# Bench_Controller.net
KiCad netlist of a schematic drawn in EAGLE
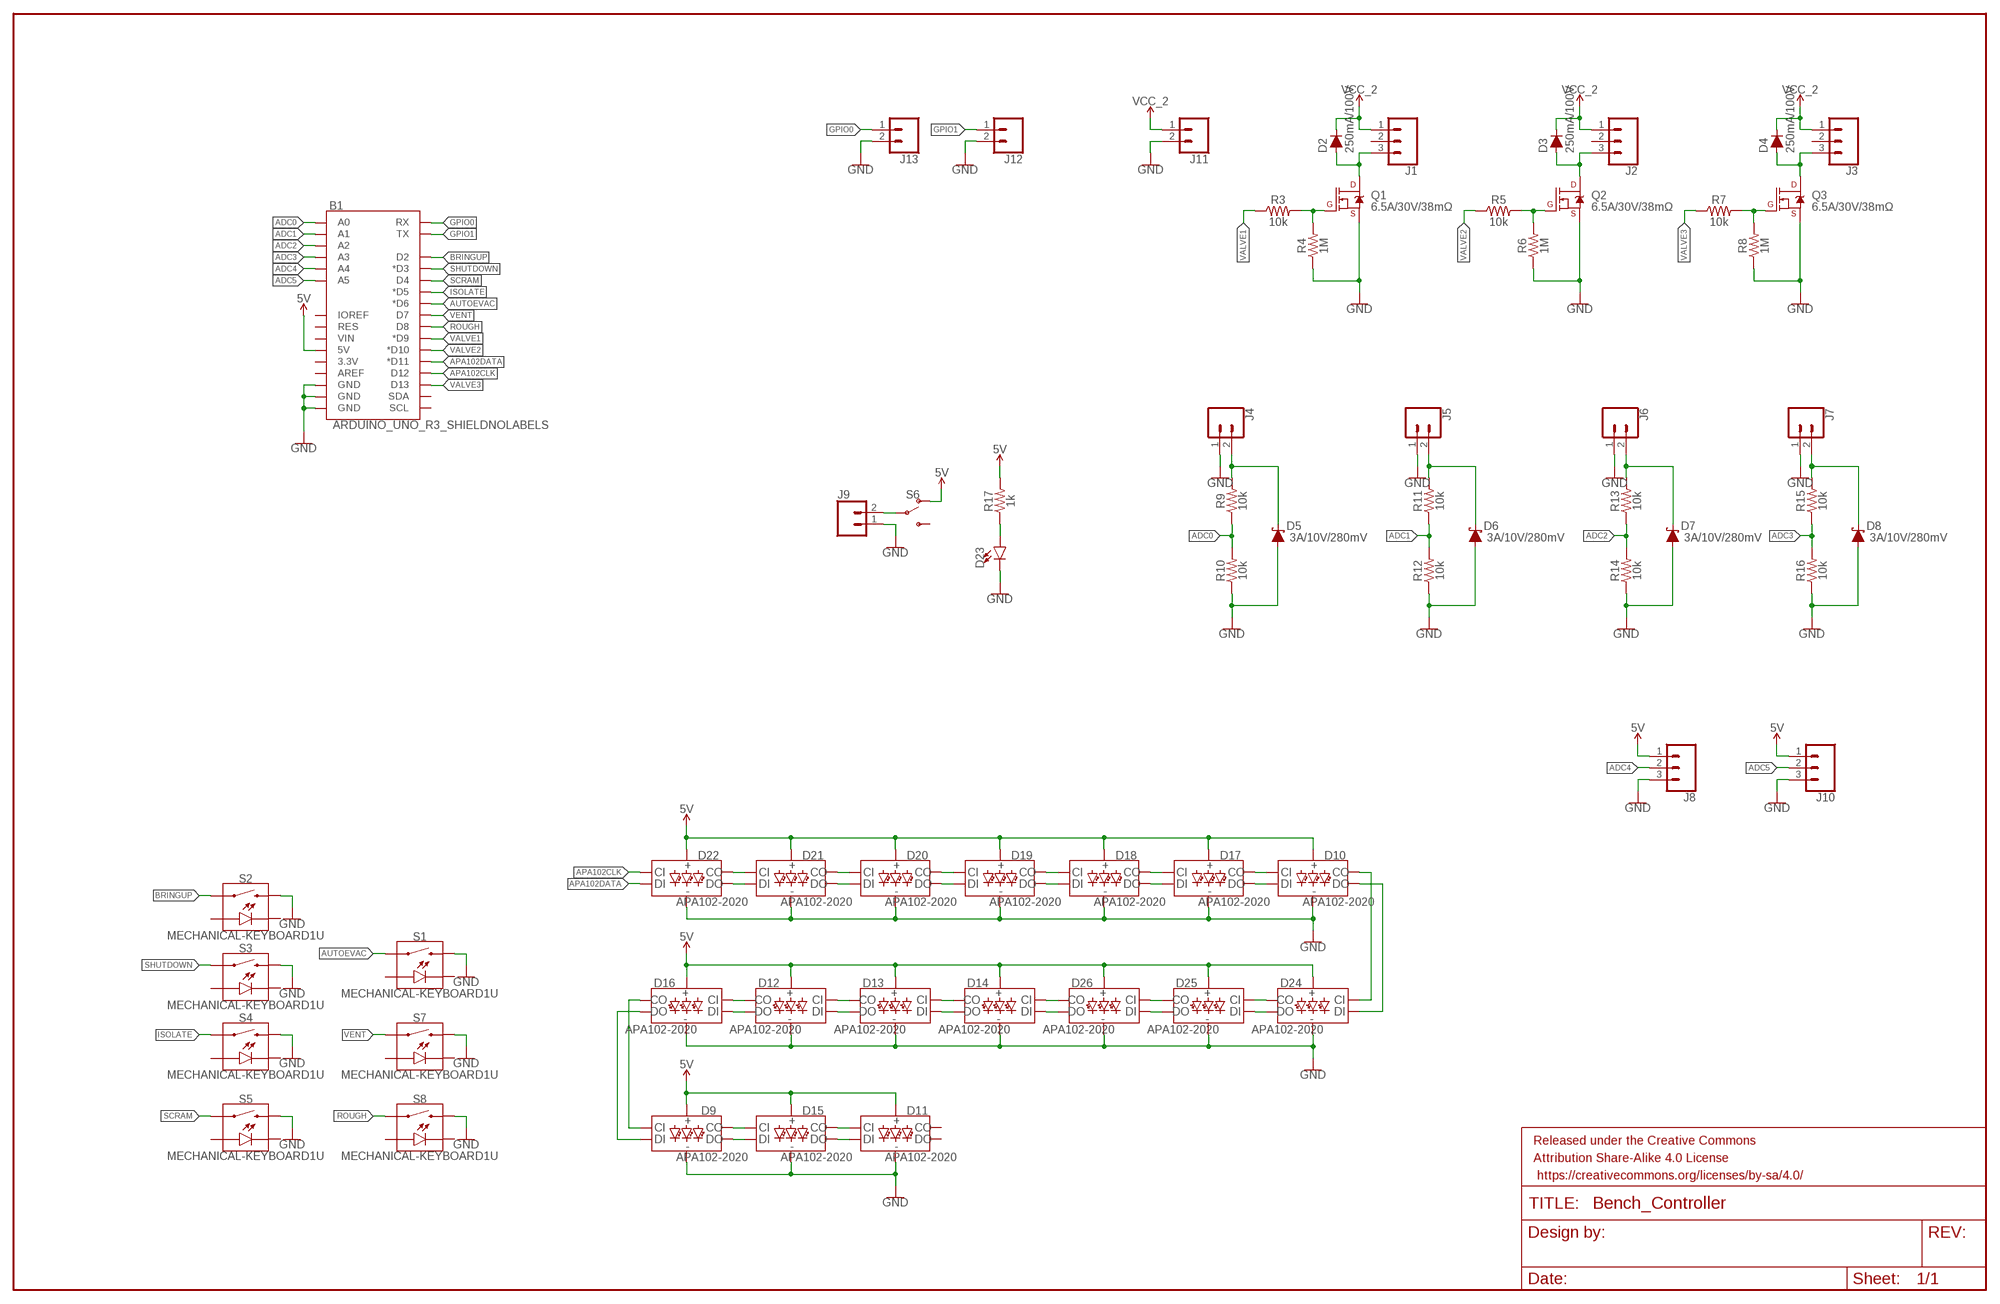
[diagram p0: schematic, sheet 1]

(export (version "E")
  (design (tool "Eeschema 10.0.6"))
  (components
    (comp (ref "B1")
      (value "ARDUINO_UNO_R3_SHIELDNOLABELS")
      (footprint "eagle-import:UNO_R3_SHIELD_NOLABELS")
      (libsource (lib "eagle-import") (part "ARDUINO_UNO_R3_SHIELDNOLABELS"))
    )
    (comp (ref "D2")
      (value "250mA/100V")
      (footprint "eagle-import:SOD-323")
      (libsource (lib "eagle-import") (part "DIODE-BAS16J"))
    )
    (comp (ref "D3")
      (value "250mA/100V")
      (footprint "eagle-import:SOD-323")
      (libsource (lib "eagle-import") (part "DIODE-BAS16J"))
    )
    (comp (ref "D4")
      (value "250mA/100V")
      (footprint "eagle-import:SOD-323")
      (libsource (lib "eagle-import") (part "DIODE-BAS16J"))
    )
    (comp (ref "D5")
      (value "3A/10V/280mV")
      (footprint "eagle-import:SOD-323")
      (libsource (lib "eagle-import") (part "DIODE-SCHOTTKY-BAT60A"))
    )
    (comp (ref "D6")
      (value "3A/10V/280mV")
      (footprint "eagle-import:SOD-323")
      (libsource (lib "eagle-import") (part "DIODE-SCHOTTKY-BAT60A"))
    )
    (comp (ref "D7")
      (value "3A/10V/280mV")
      (footprint "eagle-import:SOD-323")
      (libsource (lib "eagle-import") (part "DIODE-SCHOTTKY-BAT60A"))
    )
    (comp (ref "D8")
      (value "3A/10V/280mV")
      (footprint "eagle-import:SOD-323")
      (libsource (lib "eagle-import") (part "DIODE-SCHOTTKY-BAT60A"))
    )
    (comp (ref "D9")
      (value "APA102-2020")
      (footprint "eagle-import:APA102-2020")
      (libsource (lib "eagle-import") (part "APA102-2020"))
    )
    (comp (ref "D10")
      (value "APA102-2020")
      (footprint "eagle-import:APA102-2020")
      (libsource (lib "eagle-import") (part "APA102-2020"))
    )
    (comp (ref "D11")
      (value "APA102-2020")
      (footprint "eagle-import:APA102-2020")
      (libsource (lib "eagle-import") (part "APA102-2020"))
    )
    (comp (ref "D12")
      (value "APA102-2020")
      (footprint "eagle-import:APA102-2020")
      (libsource (lib "eagle-import") (part "APA102-2020"))
    )
    (comp (ref "D13")
      (value "APA102-2020")
      (footprint "eagle-import:APA102-2020")
      (libsource (lib "eagle-import") (part "APA102-2020"))
    )
    (comp (ref "D14")
      (value "APA102-2020")
      (footprint "eagle-import:APA102-2020")
      (libsource (lib "eagle-import") (part "APA102-2020"))
    )
    (comp (ref "D15")
      (value "APA102-2020")
      (footprint "eagle-import:APA102-2020")
      (libsource (lib "eagle-import") (part "APA102-2020"))
    )
    (comp (ref "D16")
      (value "APA102-2020")
      (footprint "eagle-import:APA102-2020")
      (libsource (lib "eagle-import") (part "APA102-2020"))
    )
    (comp (ref "D17")
      (value "APA102-2020")
      (footprint "eagle-import:APA102-2020")
      (libsource (lib "eagle-import") (part "APA102-2020"))
    )
    (comp (ref "D18")
      (value "APA102-2020")
      (footprint "eagle-import:APA102-2020")
      (libsource (lib "eagle-import") (part "APA102-2020"))
    )
    (comp (ref "D19")
      (value "APA102-2020")
      (footprint "eagle-import:APA102-2020")
      (libsource (lib "eagle-import") (part "APA102-2020"))
    )
    (comp (ref "D20")
      (value "APA102-2020")
      (footprint "eagle-import:APA102-2020")
      (libsource (lib "eagle-import") (part "APA102-2020"))
    )
    (comp (ref "D21")
      (value "APA102-2020")
      (footprint "eagle-import:APA102-2020")
      (libsource (lib "eagle-import") (part "APA102-2020"))
    )
    (comp (ref "D22")
      (value "APA102-2020")
      (footprint "eagle-import:APA102-2020")
      (libsource (lib "eagle-import") (part "APA102-2020"))
    )
    (comp (ref "D23")
      (value "LED5MM")
      (footprint "eagle-import:LED_5MM")
      (libsource (lib "eagle-import") (part "LED5MM"))
    )
    (comp (ref "D24")
      (value "APA102-2020")
      (footprint "eagle-import:APA102-2020")
      (libsource (lib "eagle-import") (part "APA102-2020"))
    )
    (comp (ref "D25")
      (value "APA102-2020")
      (footprint "eagle-import:APA102-2020")
      (libsource (lib "eagle-import") (part "APA102-2020"))
    )
    (comp (ref "D26")
      (value "APA102-2020")
      (footprint "eagle-import:APA102-2020")
      (libsource (lib "eagle-import") (part "APA102-2020"))
    )
    (comp (ref "FRAME1")
      (value "FRAME-LEDGER")
      (footprint "eagle-import:CREATIVE_COMMONS")
      (libsource (lib "eagle-import") (part "FRAME-LEDGER"))
    )
    (comp (ref "J1")
      (value "CONN_031X03_NO_SILK")
      (footprint "eagle-import:1X03_NO_SILK")
      (libsource (lib "eagle-import") (part "CONN_031X03_NO_SILK"))
    )
    (comp (ref "J2")
      (value "CONN_031X03_NO_SILK")
      (footprint "eagle-import:1X03_NO_SILK")
      (libsource (lib "eagle-import") (part "CONN_031X03_NO_SILK"))
    )
    (comp (ref "J3")
      (value "CONN_031X03_NO_SILK")
      (footprint "eagle-import:1X03_NO_SILK")
      (libsource (lib "eagle-import") (part "CONN_031X03_NO_SILK"))
    )
    (comp (ref "J4")
      (value "CONN_021X02_NO_SILK")
      (footprint "eagle-import:1X02_NO_SILK")
      (libsource (lib "eagle-import") (part "CONN_021X02_NO_SILK"))
    )
    (comp (ref "J5")
      (value "CONN_021X02_NO_SILK")
      (footprint "eagle-import:1X02_NO_SILK")
      (libsource (lib "eagle-import") (part "CONN_021X02_NO_SILK"))
    )
    (comp (ref "J6")
      (value "CONN_021X02_NO_SILK")
      (footprint "eagle-import:1X02_NO_SILK")
      (libsource (lib "eagle-import") (part "CONN_021X02_NO_SILK"))
    )
    (comp (ref "J7")
      (value "CONN_021X02_NO_SILK")
      (footprint "eagle-import:1X02_NO_SILK")
      (libsource (lib "eagle-import") (part "CONN_021X02_NO_SILK"))
    )
    (comp (ref "J8")
      (value "CONN_031X03_NO_SILK")
      (footprint "eagle-import:1X03_NO_SILK")
      (libsource (lib "eagle-import") (part "CONN_031X03_NO_SILK"))
    )
    (comp (ref "J9")
      (value "CONN_021X02_NO_SILK")
      (footprint "eagle-import:1X02_NO_SILK")
      (libsource (lib "eagle-import") (part "CONN_021X02_NO_SILK"))
    )
    (comp (ref "J10")
      (value "CONN_031X03_NO_SILK")
      (footprint "eagle-import:1X03_NO_SILK")
      (libsource (lib "eagle-import") (part "CONN_031X03_NO_SILK"))
    )
    (comp (ref "J11")
      (value "CONN_021X02_NO_SILK")
      (footprint "eagle-import:1X02_NO_SILK")
      (libsource (lib "eagle-import") (part "CONN_021X02_NO_SILK"))
    )
    (comp (ref "J12")
      (value "CONN_021X02_NO_SILK")
      (footprint "eagle-import:1X02_NO_SILK")
      (libsource (lib "eagle-import") (part "CONN_021X02_NO_SILK"))
    )
    (comp (ref "J13")
      (value "CONN_021X02_NO_SILK")
      (footprint "eagle-import:1X02_NO_SILK")
      (libsource (lib "eagle-import") (part "CONN_021X02_NO_SILK"))
    )
    (comp (ref "Q1")
      (value "6.5A/30V/38mΩ")
      (footprint "eagle-import:SO08")
      (libsource (lib "eagle-import") (part "MOSFET-NCH-FDS6630A"))
    )
    (comp (ref "Q2")
      (value "6.5A/30V/38mΩ")
      (footprint "eagle-import:SO08")
      (libsource (lib "eagle-import") (part "MOSFET-NCH-FDS6630A"))
    )
    (comp (ref "Q3")
      (value "6.5A/30V/38mΩ")
      (footprint "eagle-import:SO08")
      (libsource (lib "eagle-import") (part "MOSFET-NCH-FDS6630A"))
    )
    (comp (ref "R3")
      (value "10k")
      (footprint "eagle-import:0603")
      (libsource (lib "eagle-import") (part "10KOHM-0603-1/10W-1%"))
    )
    (comp (ref "R4")
      (value "1M")
      (footprint "eagle-import:0603")
      (libsource (lib "eagle-import") (part "1MOHM-0603-1/4W-5%"))
    )
    (comp (ref "R5")
      (value "10k")
      (footprint "eagle-import:0603")
      (libsource (lib "eagle-import") (part "10KOHM-0603-1/10W-1%"))
    )
    (comp (ref "R6")
      (value "1M")
      (footprint "eagle-import:0603")
      (libsource (lib "eagle-import") (part "1MOHM-0603-1/4W-5%"))
    )
    (comp (ref "R7")
      (value "10k")
      (footprint "eagle-import:0603")
      (libsource (lib "eagle-import") (part "10KOHM-0603-1/10W-1%"))
    )
    (comp (ref "R8")
      (value "1M")
      (footprint "eagle-import:0603")
      (libsource (lib "eagle-import") (part "1MOHM-0603-1/4W-5%"))
    )
    (comp (ref "R9")
      (value "10k")
      (footprint "eagle-import:0603")
      (libsource (lib "eagle-import") (part "10KOHM-0603-1/10W-1%"))
    )
    (comp (ref "R10")
      (value "10k")
      (footprint "eagle-import:0603")
      (libsource (lib "eagle-import") (part "10KOHM-0603-1/10W-1%"))
    )
    (comp (ref "R11")
      (value "10k")
      (footprint "eagle-import:0603")
      (libsource (lib "eagle-import") (part "10KOHM-0603-1/10W-1%"))
    )
    (comp (ref "R12")
      (value "10k")
      (footprint "eagle-import:0603")
      (libsource (lib "eagle-import") (part "10KOHM-0603-1/10W-1%"))
    )
    (comp (ref "R13")
      (value "10k")
      (footprint "eagle-import:0603")
      (libsource (lib "eagle-import") (part "10KOHM-0603-1/10W-1%"))
    )
    (comp (ref "R14")
      (value "10k")
      (footprint "eagle-import:0603")
      (libsource (lib "eagle-import") (part "10KOHM-0603-1/10W-1%"))
    )
    (comp (ref "R15")
      (value "10k")
      (footprint "eagle-import:0603")
      (libsource (lib "eagle-import") (part "10KOHM-0603-1/10W-1%"))
    )
    (comp (ref "R16")
      (value "10k")
      (footprint "eagle-import:0603")
      (libsource (lib "eagle-import") (part "10KOHM-0603-1/10W-1%"))
    )
    (comp (ref "R17")
      (value "1k")
      (footprint "eagle-import:0603")
      (libsource (lib "eagle-import") (part "1KOHM-0603-1/10W-1%"))
    )
    (comp (ref "S1")
      (value "MECHANICAL-KEYBOARD1U")
      (footprint "eagle-import:CHERRY-MX-LED-1U")
      (libsource (lib "eagle-import") (part "MECHANICAL-KEYBOARD1U"))
    )
    (comp (ref "S2")
      (value "MECHANICAL-KEYBOARD1U")
      (footprint "eagle-import:CHERRY-MX-LED-1U")
      (libsource (lib "eagle-import") (part "MECHANICAL-KEYBOARD1U"))
    )
    (comp (ref "S3")
      (value "MECHANICAL-KEYBOARD1U")
      (footprint "eagle-import:CHERRY-MX-LED-1U")
      (libsource (lib "eagle-import") (part "MECHANICAL-KEYBOARD1U"))
    )
    (comp (ref "S4")
      (value "MECHANICAL-KEYBOARD1U")
      (footprint "eagle-import:CHERRY-MX-LED-1U")
      (libsource (lib "eagle-import") (part "MECHANICAL-KEYBOARD1U"))
    )
    (comp (ref "S5")
      (value "MECHANICAL-KEYBOARD1U")
      (footprint "eagle-import:CHERRY-MX-LED-1U")
      (libsource (lib "eagle-import") (part "MECHANICAL-KEYBOARD1U"))
    )
    (comp (ref "S6")
      (value "SWITCH-SPDT-PTH-11.6X4.0MM")
      (footprint "eagle-import:SWITCH_SPDT_PTH_11.6X4.0MM")
      (libsource (lib "eagle-import") (part "SWITCH-SPDT-PTH-11.6X4.0MM"))
    )
    (comp (ref "S7")
      (value "MECHANICAL-KEYBOARD1U")
      (footprint "eagle-import:CHERRY-MX-LED-1U")
      (libsource (lib "eagle-import") (part "MECHANICAL-KEYBOARD1U"))
    )
    (comp (ref "S8")
      (value "MECHANICAL-KEYBOARD1U")
      (footprint "eagle-import:CHERRY-MX-LED-1U")
      (libsource (lib "eagle-import") (part "MECHANICAL-KEYBOARD1U"))
    )
  )
  (nets
    (net (code "1") (name "5V") (class "Default")
      (node (ref "B1") (pin "5V") (pinfunction "5V_5V") (pintype "bidirectional"))
      (node (ref "D10") (pin "VDD") (pinfunction "VCC_VDD") (pintype "bidirectional"))
      (node (ref "D11") (pin "VDD") (pinfunction "VCC_VDD") (pintype "bidirectional"))
      (node (ref "D12") (pin "VDD") (pinfunction "VCC_VDD") (pintype "bidirectional"))
      (node (ref "D13") (pin "VDD") (pinfunction "VCC_VDD") (pintype "bidirectional"))
      (node (ref "D14") (pin "VDD") (pinfunction "VCC_VDD") (pintype "bidirectional"))
      (node (ref "D15") (pin "VDD") (pinfunction "VCC_VDD") (pintype "bidirectional"))
      (node (ref "D16") (pin "VDD") (pinfunction "VCC_VDD") (pintype "bidirectional"))
      (node (ref "D17") (pin "VDD") (pinfunction "VCC_VDD") (pintype "bidirectional"))
      (node (ref "D18") (pin "VDD") (pinfunction "VCC_VDD") (pintype "bidirectional"))
      (node (ref "D19") (pin "VDD") (pinfunction "VCC_VDD") (pintype "bidirectional"))
      (node (ref "D20") (pin "VDD") (pinfunction "VCC_VDD") (pintype "bidirectional"))
      (node (ref "D21") (pin "VDD") (pinfunction "VCC_VDD") (pintype "bidirectional"))
      (node (ref "D22") (pin "VDD") (pinfunction "VCC_VDD") (pintype "bidirectional"))
      (node (ref "D24") (pin "VDD") (pinfunction "VCC_VDD") (pintype "bidirectional"))
      (node (ref "D25") (pin "VDD") (pinfunction "VCC_VDD") (pintype "bidirectional"))
      (node (ref "D26") (pin "VDD") (pinfunction "VCC_VDD") (pintype "bidirectional"))
      (node (ref "D9") (pin "VDD") (pinfunction "VCC_VDD") (pintype "bidirectional"))
      (node (ref "J10") (pin "1") (pinfunction "1_1") (pintype "passive"))
      (node (ref "J8") (pin "1") (pinfunction "1_1") (pintype "passive"))
      (node (ref "R17") (pin "2") (pinfunction "2_2") (pintype "passive"))
      (node (ref "S6") (pin "1") (pinfunction "O_1") (pintype "passive"))
    )
    (net (code "2") (name "ADC0") (class "Default")
      (node (ref "B1") (pin "A0") (pinfunction "A0_A0") (pintype "bidirectional"))
      (node (ref "R10") (pin "2") (pinfunction "2_2") (pintype "passive"))
      (node (ref "R9") (pin "1") (pinfunction "1_1") (pintype "passive"))
    )
    (net (code "3") (name "ADC1") (class "Default")
      (node (ref "B1") (pin "A1") (pinfunction "A1_A1") (pintype "bidirectional"))
      (node (ref "R11") (pin "1") (pinfunction "1_1") (pintype "passive"))
      (node (ref "R12") (pin "2") (pinfunction "2_2") (pintype "passive"))
    )
    (net (code "4") (name "ADC2") (class "Default")
      (node (ref "B1") (pin "A2") (pinfunction "A2_A2") (pintype "bidirectional"))
      (node (ref "R13") (pin "1") (pinfunction "1_1") (pintype "passive"))
      (node (ref "R14") (pin "2") (pinfunction "2_2") (pintype "passive"))
    )
    (net (code "5") (name "ADC3") (class "Default")
      (node (ref "B1") (pin "A3") (pinfunction "A3_A3") (pintype "bidirectional"))
      (node (ref "R15") (pin "1") (pinfunction "1_1") (pintype "passive"))
      (node (ref "R16") (pin "2") (pinfunction "2_2") (pintype "passive"))
    )
    (net (code "6") (name "ADC4") (class "Default")
      (node (ref "B1") (pin "A4") (pinfunction "A4_A4") (pintype "bidirectional"))
      (node (ref "J8") (pin "2") (pinfunction "2_2") (pintype "passive"))
    )
    (net (code "7") (name "ADC5") (class "Default")
      (node (ref "B1") (pin "A5") (pinfunction "A5_A5") (pintype "bidirectional"))
      (node (ref "J10") (pin "2") (pinfunction "2_2") (pintype "passive"))
    )
    (net (code "8") (name "APA102CLK") (class "Default")
      (node (ref "B1") (pin "D12") (pinfunction "D12_D12") (pintype "bidirectional"))
      (node (ref "D22") (pin "CKI") (pinfunction "CI_CKI") (pintype "bidirectional"))
    )
    (net (code "9") (name "APA102DATA") (class "Default")
      (node (ref "B1") (pin "D11") (pinfunction "*D11_D11") (pintype "bidirectional"))
      (node (ref "D22") (pin "SDI") (pinfunction "DI_SDI") (pintype "bidirectional"))
    )
    (net (code "10") (name "AUTOEVAC") (class "Default")
      (node (ref "B1") (pin "D6") (pinfunction "*D6_D6") (pintype "bidirectional"))
      (node (ref "S1") (pin "S1") (pinfunction "1_S1") (pintype "passive"))
    )
    (net (code "11") (name "BRINGUP") (class "Default")
      (node (ref "B1") (pin "D2") (pinfunction "D2_D2") (pintype "bidirectional"))
      (node (ref "S2") (pin "S1") (pinfunction "1_S1") (pintype "passive"))
    )
    (net (code "12") (name "GND") (class "Default")
      (node (ref "B1") (pin "GND@0") (pinfunction "GND_GND@0") (pintype "bidirectional"))
      (node (ref "B1") (pin "GND@1") (pinfunction "GND_GND@1") (pintype "bidirectional"))
      (node (ref "B1") (pin "GND@2") (pinfunction "GND_GND@2") (pintype "bidirectional"))
      (node (ref "D10") (pin "GND") (pinfunction "GND_GND") (pintype "bidirectional"))
      (node (ref "D11") (pin "GND") (pinfunction "GND_GND") (pintype "bidirectional"))
      (node (ref "D12") (pin "GND") (pinfunction "GND_GND") (pintype "bidirectional"))
      (node (ref "D13") (pin "GND") (pinfunction "GND_GND") (pintype "bidirectional"))
      (node (ref "D14") (pin "GND") (pinfunction "GND_GND") (pintype "bidirectional"))
      (node (ref "D15") (pin "GND") (pinfunction "GND_GND") (pintype "bidirectional"))
      (node (ref "D16") (pin "GND") (pinfunction "GND_GND") (pintype "bidirectional"))
      (node (ref "D17") (pin "GND") (pinfunction "GND_GND") (pintype "bidirectional"))
      (node (ref "D18") (pin "GND") (pinfunction "GND_GND") (pintype "bidirectional"))
      (node (ref "D19") (pin "GND") (pinfunction "GND_GND") (pintype "bidirectional"))
      (node (ref "D20") (pin "GND") (pinfunction "GND_GND") (pintype "bidirectional"))
      (node (ref "D21") (pin "GND") (pinfunction "GND_GND") (pintype "bidirectional"))
      (node (ref "D22") (pin "GND") (pinfunction "GND_GND") (pintype "bidirectional"))
      (node (ref "D23") (pin "K") (pinfunction "C_K") (pintype "passive"))
      (node (ref "D24") (pin "GND") (pinfunction "GND_GND") (pintype "bidirectional"))
      (node (ref "D25") (pin "GND") (pinfunction "GND_GND") (pintype "bidirectional"))
      (node (ref "D26") (pin "GND") (pinfunction "GND_GND") (pintype "bidirectional"))
      (node (ref "D5") (pin "A") (pinfunction "A_A") (pintype "passive"))
      (node (ref "D6") (pin "A") (pinfunction "A_A") (pintype "passive"))
      (node (ref "D7") (pin "A") (pinfunction "A_A") (pintype "passive"))
      (node (ref "D8") (pin "A") (pinfunction "A_A") (pintype "passive"))
      (node (ref "D9") (pin "GND") (pinfunction "GND_GND") (pintype "bidirectional"))
      (node (ref "J10") (pin "3") (pinfunction "3_3") (pintype "passive"))
      (node (ref "J11") (pin "2") (pinfunction "2_2") (pintype "passive"))
      (node (ref "J12") (pin "2") (pinfunction "2_2") (pintype "passive"))
      (node (ref "J13") (pin "2") (pinfunction "2_2") (pintype "passive"))
      (node (ref "J4") (pin "1") (pinfunction "1_1") (pintype "passive"))
      (node (ref "J5") (pin "1") (pinfunction "1_1") (pintype "passive"))
      (node (ref "J6") (pin "1") (pinfunction "1_1") (pintype "passive"))
      (node (ref "J7") (pin "1") (pinfunction "1_1") (pintype "passive"))
      (node (ref "J8") (pin "3") (pinfunction "3_3") (pintype "passive"))
      (node (ref "J9") (pin "1") (pinfunction "1_1") (pintype "passive"))
      (node (ref "Q1") (pin "1") (pinfunction "S_1") (pintype "bidirectional"))
      (node (ref "Q1") (pin "2") (pinfunction "S_2") (pintype "bidirectional"))
      (node (ref "Q1") (pin "3") (pinfunction "S_3") (pintype "bidirectional"))
      (node (ref "Q2") (pin "1") (pinfunction "S_1") (pintype "bidirectional"))
      (node (ref "Q2") (pin "2") (pinfunction "S_2") (pintype "bidirectional"))
      (node (ref "Q2") (pin "3") (pinfunction "S_3") (pintype "bidirectional"))
      (node (ref "Q3") (pin "1") (pinfunction "S_1") (pintype "bidirectional"))
      (node (ref "Q3") (pin "2") (pinfunction "S_2") (pintype "bidirectional"))
      (node (ref "Q3") (pin "3") (pinfunction "S_3") (pintype "bidirectional"))
      (node (ref "R10") (pin "1") (pinfunction "1_1") (pintype "passive"))
      (node (ref "R12") (pin "1") (pinfunction "1_1") (pintype "passive"))
      (node (ref "R14") (pin "1") (pinfunction "1_1") (pintype "passive"))
      (node (ref "R16") (pin "1") (pinfunction "1_1") (pintype "passive"))
      (node (ref "R4") (pin "1") (pinfunction "1_1") (pintype "passive"))
      (node (ref "R6") (pin "1") (pinfunction "1_1") (pintype "passive"))
      (node (ref "R8") (pin "1") (pinfunction "1_1") (pintype "passive"))
      (node (ref "S1") (pin "S2") (pinfunction "2_S2") (pintype "passive"))
      (node (ref "S2") (pin "S2") (pinfunction "2_S2") (pintype "passive"))
      (node (ref "S3") (pin "S2") (pinfunction "2_S2") (pintype "passive"))
      (node (ref "S4") (pin "S2") (pinfunction "2_S2") (pintype "passive"))
      (node (ref "S5") (pin "S2") (pinfunction "2_S2") (pintype "passive"))
      (node (ref "S7") (pin "S2") (pinfunction "2_S2") (pintype "passive"))
      (node (ref "S8") (pin "S2") (pinfunction "2_S2") (pintype "passive"))
    )
    (net (code "13") (name "GPIO0") (class "Default")
      (node (ref "B1") (pin "RX") (pinfunction "RX_RX") (pintype "bidirectional"))
      (node (ref "J13") (pin "1") (pinfunction "1_1") (pintype "passive"))
    )
    (net (code "14") (name "GPIO1") (class "Default")
      (node (ref "B1") (pin "TX") (pinfunction "TX_TX") (pintype "bidirectional"))
      (node (ref "J12") (pin "1") (pinfunction "1_1") (pintype "passive"))
    )
    (net (code "15") (name "ISOLATE") (class "Default")
      (node (ref "B1") (pin "D5") (pinfunction "*D5_D5") (pintype "bidirectional"))
      (node (ref "S4") (pin "S1") (pinfunction "1_S1") (pintype "passive"))
    )
    (net (code "16") (name "Net-(D2-PadA)") (class "Default")
      (node (ref "D2") (pin "A") (pinfunction "A_A") (pintype "passive"))
      (node (ref "J1") (pin "3") (pinfunction "3_3") (pintype "passive"))
      (node (ref "Q1") (pin "5") (pinfunction "D_5") (pintype "bidirectional"))
      (node (ref "Q1") (pin "6") (pinfunction "D_6") (pintype "bidirectional"))
      (node (ref "Q1") (pin "7") (pinfunction "D_7") (pintype "bidirectional"))
      (node (ref "Q1") (pin "8") (pinfunction "D_8") (pintype "bidirectional"))
    )
    (net (code "17") (name "Net-(D3-PadA)") (class "Default")
      (node (ref "D3") (pin "A") (pinfunction "A_A") (pintype "passive"))
      (node (ref "J2") (pin "3") (pinfunction "3_3") (pintype "passive"))
      (node (ref "Q2") (pin "5") (pinfunction "D_5") (pintype "bidirectional"))
      (node (ref "Q2") (pin "6") (pinfunction "D_6") (pintype "bidirectional"))
      (node (ref "Q2") (pin "7") (pinfunction "D_7") (pintype "bidirectional"))
      (node (ref "Q2") (pin "8") (pinfunction "D_8") (pintype "bidirectional"))
    )
    (net (code "18") (name "Net-(D4-PadA)") (class "Default")
      (node (ref "D4") (pin "A") (pinfunction "A_A") (pintype "passive"))
      (node (ref "J3") (pin "3") (pinfunction "3_3") (pintype "passive"))
      (node (ref "Q3") (pin "5") (pinfunction "D_5") (pintype "bidirectional"))
      (node (ref "Q3") (pin "6") (pinfunction "D_6") (pintype "bidirectional"))
      (node (ref "Q3") (pin "7") (pinfunction "D_7") (pintype "bidirectional"))
      (node (ref "Q3") (pin "8") (pinfunction "D_8") (pintype "bidirectional"))
    )
    (net (code "19") (name "Net-(D5-PadC)") (class "Default")
      (node (ref "D5") (pin "C") (pinfunction "C_C") (pintype "passive"))
      (node (ref "J4") (pin "2") (pinfunction "2_2") (pintype "passive"))
      (node (ref "R9") (pin "2") (pinfunction "2_2") (pintype "passive"))
    )
    (net (code "20") (name "Net-(D6-PadC)") (class "Default")
      (node (ref "D6") (pin "C") (pinfunction "C_C") (pintype "passive"))
      (node (ref "J5") (pin "2") (pinfunction "2_2") (pintype "passive"))
      (node (ref "R11") (pin "2") (pinfunction "2_2") (pintype "passive"))
    )
    (net (code "21") (name "Net-(D7-PadC)") (class "Default")
      (node (ref "D7") (pin "C") (pinfunction "C_C") (pintype "passive"))
      (node (ref "J6") (pin "2") (pinfunction "2_2") (pintype "passive"))
      (node (ref "R13") (pin "2") (pinfunction "2_2") (pintype "passive"))
    )
    (net (code "22") (name "Net-(D8-PadC)") (class "Default")
      (node (ref "D8") (pin "C") (pinfunction "C_C") (pintype "passive"))
      (node (ref "J7") (pin "2") (pinfunction "2_2") (pintype "passive"))
      (node (ref "R15") (pin "2") (pinfunction "2_2") (pintype "passive"))
    )
    (net (code "23") (name "Net-(D10-CI)") (class "Default")
      (node (ref "D10") (pin "CKI") (pinfunction "CI_CKI") (pintype "bidirectional"))
      (node (ref "D17") (pin "CKO") (pinfunction "CO_CKO") (pintype "bidirectional"))
    )
    (net (code "24") (name "Net-(D10-CO)") (class "Default")
      (node (ref "D10") (pin "CKO") (pinfunction "CO_CKO") (pintype "bidirectional"))
      (node (ref "D24") (pin "CKI") (pinfunction "CI_CKI") (pintype "bidirectional"))
    )
    (net (code "25") (name "Net-(D10-DI)") (class "Default")
      (node (ref "D10") (pin "SDI") (pinfunction "DI_SDI") (pintype "bidirectional"))
      (node (ref "D17") (pin "SDO") (pinfunction "DO_SDO") (pintype "bidirectional"))
    )
    (net (code "26") (name "Net-(D10-DO)") (class "Default")
      (node (ref "D10") (pin "SDO") (pinfunction "DO_SDO") (pintype "bidirectional"))
      (node (ref "D24") (pin "SDI") (pinfunction "DI_SDI") (pintype "bidirectional"))
    )
    (net (code "27") (name "Net-(D11-CI)") (class "Default")
      (node (ref "D11") (pin "CKI") (pinfunction "CI_CKI") (pintype "bidirectional"))
      (node (ref "D15") (pin "CKO") (pinfunction "CO_CKO") (pintype "bidirectional"))
    )
    (net (code "28") (name "Net-(D11-DI)") (class "Default")
      (node (ref "D11") (pin "SDI") (pinfunction "DI_SDI") (pintype "bidirectional"))
      (node (ref "D15") (pin "SDO") (pinfunction "DO_SDO") (pintype "bidirectional"))
    )
    (net (code "29") (name "Net-(D12-CI)") (class "Default")
      (node (ref "D12") (pin "CKI") (pinfunction "CI_CKI") (pintype "bidirectional"))
      (node (ref "D13") (pin "CKO") (pinfunction "CO_CKO") (pintype "bidirectional"))
    )
    (net (code "30") (name "Net-(D12-CO)") (class "Default")
      (node (ref "D12") (pin "CKO") (pinfunction "CO_CKO") (pintype "bidirectional"))
      (node (ref "D16") (pin "CKI") (pinfunction "CI_CKI") (pintype "bidirectional"))
    )
    (net (code "31") (name "Net-(D12-DI)") (class "Default")
      (node (ref "D12") (pin "SDI") (pinfunction "DI_SDI") (pintype "bidirectional"))
      (node (ref "D13") (pin "SDO") (pinfunction "DO_SDO") (pintype "bidirectional"))
    )
    (net (code "32") (name "Net-(D12-DO)") (class "Default")
      (node (ref "D12") (pin "SDO") (pinfunction "DO_SDO") (pintype "bidirectional"))
      (node (ref "D16") (pin "SDI") (pinfunction "DI_SDI") (pintype "bidirectional"))
    )
    (net (code "33") (name "Net-(D13-CI)") (class "Default")
      (node (ref "D13") (pin "CKI") (pinfunction "CI_CKI") (pintype "bidirectional"))
      (node (ref "D14") (pin "CKO") (pinfunction "CO_CKO") (pintype "bidirectional"))
    )
    (net (code "34") (name "Net-(D13-DI)") (class "Default")
      (node (ref "D13") (pin "SDI") (pinfunction "DI_SDI") (pintype "bidirectional"))
      (node (ref "D14") (pin "SDO") (pinfunction "DO_SDO") (pintype "bidirectional"))
    )
    (net (code "35") (name "Net-(D14-CI)") (class "Default")
      (node (ref "D14") (pin "CKI") (pinfunction "CI_CKI") (pintype "bidirectional"))
      (node (ref "D26") (pin "CKO") (pinfunction "CO_CKO") (pintype "bidirectional"))
    )
    (net (code "36") (name "Net-(D14-DI)") (class "Default")
      (node (ref "D14") (pin "SDI") (pinfunction "DI_SDI") (pintype "bidirectional"))
      (node (ref "D26") (pin "SDO") (pinfunction "DO_SDO") (pintype "bidirectional"))
    )
    (net (code "37") (name "Net-(D15-CI)") (class "Default")
      (node (ref "D15") (pin "CKI") (pinfunction "CI_CKI") (pintype "bidirectional"))
      (node (ref "D9") (pin "CKO") (pinfunction "CO_CKO") (pintype "bidirectional"))
    )
    (net (code "38") (name "Net-(D15-DI)") (class "Default")
      (node (ref "D15") (pin "SDI") (pinfunction "DI_SDI") (pintype "bidirectional"))
      (node (ref "D9") (pin "SDO") (pinfunction "DO_SDO") (pintype "bidirectional"))
    )
    (net (code "39") (name "Net-(D16-CO)") (class "Default")
      (node (ref "D16") (pin "CKO") (pinfunction "CO_CKO") (pintype "bidirectional"))
      (node (ref "D9") (pin "CKI") (pinfunction "CI_CKI") (pintype "bidirectional"))
    )
    (net (code "40") (name "Net-(D16-DO)") (class "Default")
      (node (ref "D16") (pin "SDO") (pinfunction "DO_SDO") (pintype "bidirectional"))
      (node (ref "D9") (pin "SDI") (pinfunction "DI_SDI") (pintype "bidirectional"))
    )
    (net (code "41") (name "Net-(D17-CI)") (class "Default")
      (node (ref "D17") (pin "CKI") (pinfunction "CI_CKI") (pintype "bidirectional"))
      (node (ref "D18") (pin "CKO") (pinfunction "CO_CKO") (pintype "bidirectional"))
    )
    (net (code "42") (name "Net-(D17-DI)") (class "Default")
      (node (ref "D17") (pin "SDI") (pinfunction "DI_SDI") (pintype "bidirectional"))
      (node (ref "D18") (pin "SDO") (pinfunction "DO_SDO") (pintype "bidirectional"))
    )
    (net (code "43") (name "Net-(D18-CI)") (class "Default")
      (node (ref "D18") (pin "CKI") (pinfunction "CI_CKI") (pintype "bidirectional"))
      (node (ref "D19") (pin "CKO") (pinfunction "CO_CKO") (pintype "bidirectional"))
    )
    (net (code "44") (name "Net-(D18-DI)") (class "Default")
      (node (ref "D18") (pin "SDI") (pinfunction "DI_SDI") (pintype "bidirectional"))
      (node (ref "D19") (pin "SDO") (pinfunction "DO_SDO") (pintype "bidirectional"))
    )
    (net (code "45") (name "Net-(D19-CI)") (class "Default")
      (node (ref "D19") (pin "CKI") (pinfunction "CI_CKI") (pintype "bidirectional"))
      (node (ref "D20") (pin "CKO") (pinfunction "CO_CKO") (pintype "bidirectional"))
    )
    (net (code "46") (name "Net-(D19-DI)") (class "Default")
      (node (ref "D19") (pin "SDI") (pinfunction "DI_SDI") (pintype "bidirectional"))
      (node (ref "D20") (pin "SDO") (pinfunction "DO_SDO") (pintype "bidirectional"))
    )
    (net (code "47") (name "Net-(D20-CI)") (class "Default")
      (node (ref "D20") (pin "CKI") (pinfunction "CI_CKI") (pintype "bidirectional"))
      (node (ref "D21") (pin "CKO") (pinfunction "CO_CKO") (pintype "bidirectional"))
    )
    (net (code "48") (name "Net-(D20-DI)") (class "Default")
      (node (ref "D20") (pin "SDI") (pinfunction "DI_SDI") (pintype "bidirectional"))
      (node (ref "D21") (pin "SDO") (pinfunction "DO_SDO") (pintype "bidirectional"))
    )
    (net (code "49") (name "Net-(D21-CI)") (class "Default")
      (node (ref "D21") (pin "CKI") (pinfunction "CI_CKI") (pintype "bidirectional"))
      (node (ref "D22") (pin "CKO") (pinfunction "CO_CKO") (pintype "bidirectional"))
    )
    (net (code "50") (name "Net-(D21-DI)") (class "Default")
      (node (ref "D21") (pin "SDI") (pinfunction "DI_SDI") (pintype "bidirectional"))
      (node (ref "D22") (pin "SDO") (pinfunction "DO_SDO") (pintype "bidirectional"))
    )
    (net (code "51") (name "Net-(D23-PadA)") (class "Default")
      (node (ref "D23") (pin "A") (pinfunction "A_A") (pintype "passive"))
      (node (ref "R17") (pin "1") (pinfunction "1_1") (pintype "passive"))
    )
    (net (code "52") (name "Net-(D24-CO)") (class "Default")
      (node (ref "D24") (pin "CKO") (pinfunction "CO_CKO") (pintype "bidirectional"))
      (node (ref "D25") (pin "CKI") (pinfunction "CI_CKI") (pintype "bidirectional"))
    )
    (net (code "53") (name "Net-(D24-DO)") (class "Default")
      (node (ref "D24") (pin "SDO") (pinfunction "DO_SDO") (pintype "bidirectional"))
      (node (ref "D25") (pin "SDI") (pinfunction "DI_SDI") (pintype "bidirectional"))
    )
    (net (code "54") (name "Net-(D25-CO)") (class "Default")
      (node (ref "D25") (pin "CKO") (pinfunction "CO_CKO") (pintype "bidirectional"))
      (node (ref "D26") (pin "CKI") (pinfunction "CI_CKI") (pintype "bidirectional"))
    )
    (net (code "55") (name "Net-(D25-DO)") (class "Default")
      (node (ref "D25") (pin "SDO") (pinfunction "DO_SDO") (pintype "bidirectional"))
      (node (ref "D26") (pin "SDI") (pinfunction "DI_SDI") (pintype "bidirectional"))
    )
    (net (code "56") (name "Net-(Q1-G)") (class "Default")
      (node (ref "Q1") (pin "4") (pinfunction "G_4") (pintype "bidirectional"))
      (node (ref "R3") (pin "2") (pinfunction "2_2") (pintype "passive"))
      (node (ref "R4") (pin "2") (pinfunction "2_2") (pintype "passive"))
    )
    (net (code "57") (name "Net-(Q2-G)") (class "Default")
      (node (ref "Q2") (pin "4") (pinfunction "G_4") (pintype "bidirectional"))
      (node (ref "R5") (pin "2") (pinfunction "2_2") (pintype "passive"))
      (node (ref "R6") (pin "2") (pinfunction "2_2") (pintype "passive"))
    )
    (net (code "58") (name "Net-(Q3-G)") (class "Default")
      (node (ref "Q3") (pin "4") (pinfunction "G_4") (pintype "bidirectional"))
      (node (ref "R7") (pin "2") (pinfunction "2_2") (pintype "passive"))
      (node (ref "R8") (pin "2") (pinfunction "2_2") (pintype "passive"))
    )
    (net (code "59") (name "Net-(S6-P)") (class "Default")
      (node (ref "J9") (pin "2") (pinfunction "2_2") (pintype "passive"))
      (node (ref "S6") (pin "2") (pinfunction "P_2") (pintype "passive"))
    )
    (net (code "60") (name "ROUGH") (class "Default")
      (node (ref "B1") (pin "D8") (pinfunction "D8_D8") (pintype "bidirectional"))
      (node (ref "S8") (pin "S1") (pinfunction "1_S1") (pintype "passive"))
    )
    (net (code "61") (name "SCRAM") (class "Default")
      (node (ref "B1") (pin "D4") (pinfunction "D4_D4") (pintype "bidirectional"))
      (node (ref "S5") (pin "S1") (pinfunction "1_S1") (pintype "passive"))
    )
    (net (code "62") (name "SHUTDOWN") (class "Default")
      (node (ref "B1") (pin "D3") (pinfunction "*D3_D3") (pintype "bidirectional"))
      (node (ref "S3") (pin "S1") (pinfunction "1_S1") (pintype "passive"))
    )
    (net (code "63") (name "VALVE1") (class "Default")
      (node (ref "B1") (pin "D9") (pinfunction "*D9_D9") (pintype "bidirectional"))
      (node (ref "R3") (pin "1") (pinfunction "1_1") (pintype "passive"))
    )
    (net (code "64") (name "VALVE2") (class "Default")
      (node (ref "B1") (pin "D10") (pinfunction "*D10_D10") (pintype "bidirectional"))
      (node (ref "R5") (pin "1") (pinfunction "1_1") (pintype "passive"))
    )
    (net (code "65") (name "VALVE3") (class "Default")
      (node (ref "B1") (pin "D13") (pinfunction "D13_D13") (pintype "bidirectional"))
      (node (ref "R7") (pin "1") (pinfunction "1_1") (pintype "passive"))
    )
    (net (code "66") (name "VCC_2") (class "Default")
      (node (ref "D2") (pin "C") (pinfunction "C_C") (pintype "passive"))
      (node (ref "D3") (pin "C") (pinfunction "C_C") (pintype "passive"))
      (node (ref "D4") (pin "C") (pinfunction "C_C") (pintype "passive"))
      (node (ref "J1") (pin "1") (pinfunction "1_1") (pintype "passive"))
      (node (ref "J11") (pin "1") (pinfunction "1_1") (pintype "passive"))
      (node (ref "J2") (pin "1") (pinfunction "1_1") (pintype "passive"))
      (node (ref "J3") (pin "1") (pinfunction "1_1") (pintype "passive"))
    )
    (net (code "67") (name "VENT") (class "Default")
      (node (ref "B1") (pin "D7") (pinfunction "D7_D7") (pintype "bidirectional"))
      (node (ref "S7") (pin "S1") (pinfunction "1_S1") (pintype "passive"))
    )
    (net (code "68") (name "unconnected-(B1-Pad3.3V)") (class "Default")
      (node (ref "B1") (pin "3.3V") (pinfunction "3.3V_3.3V") (pintype "bidirectional"))
    )
    (net (code "69") (name "unconnected-(B1-PadAREF)") (class "Default")
      (node (ref "B1") (pin "AREF") (pinfunction "AREF_AREF") (pintype "bidirectional"))
    )
    (net (code "70") (name "unconnected-(B1-PadIOREF)") (class "Default")
      (node (ref "B1") (pin "IOREF") (pinfunction "IOREF_IOREF") (pintype "bidirectional"))
    )
    (net (code "71") (name "unconnected-(B1-PadRES)") (class "Default")
      (node (ref "B1") (pin "RES") (pinfunction "RES_RES") (pintype "bidirectional"))
    )
    (net (code "72") (name "unconnected-(B1-PadSCL)") (class "Default")
      (node (ref "B1") (pin "SCL") (pinfunction "SCL_SCL") (pintype "bidirectional"))
    )
    (net (code "73") (name "unconnected-(B1-PadSDA)") (class "Default")
      (node (ref "B1") (pin "SDA") (pinfunction "SDA_SDA") (pintype "bidirectional"))
    )
    (net (code "74") (name "unconnected-(B1-PadVIN)") (class "Default")
      (node (ref "B1") (pin "VIN") (pinfunction "VIN_VIN") (pintype "bidirectional"))
    )
    (net (code "75") (name "unconnected-(D11-CO-PadCKO)") (class "Default")
      (node (ref "D11") (pin "CKO") (pinfunction "CO_CKO") (pintype "bidirectional"))
    )
    (net (code "76") (name "unconnected-(D11-DO-PadSDO)") (class "Default")
      (node (ref "D11") (pin "SDO") (pinfunction "DO_SDO") (pintype "bidirectional"))
    )
    (net (code "77") (name "unconnected-(J1-Pad2)") (class "Default")
      (node (ref "J1") (pin "2") (pinfunction "2_2") (pintype "passive"))
    )
    (net (code "78") (name "unconnected-(J2-Pad2)") (class "Default")
      (node (ref "J2") (pin "2") (pinfunction "2_2") (pintype "passive"))
    )
    (net (code "79") (name "unconnected-(J3-Pad2)") (class "Default")
      (node (ref "J3") (pin "2") (pinfunction "2_2") (pintype "passive"))
    )
    (net (code "80") (name "unconnected-(S1-C-PadK)") (class "Default")
      (node (ref "S1") (pin "K") (pinfunction "C_K") (pintype "passive"))
    )
    (net (code "81") (name "unconnected-(S1-PadA)") (class "Default")
      (node (ref "S1") (pin "A") (pinfunction "A_A") (pintype "passive"))
    )
    (net (code "82") (name "unconnected-(S2-C-PadK)") (class "Default")
      (node (ref "S2") (pin "K") (pinfunction "C_K") (pintype "passive"))
    )
    (net (code "83") (name "unconnected-(S2-PadA)") (class "Default")
      (node (ref "S2") (pin "A") (pinfunction "A_A") (pintype "passive"))
    )
    (net (code "84") (name "unconnected-(S3-C-PadK)") (class "Default")
      (node (ref "S3") (pin "K") (pinfunction "C_K") (pintype "passive"))
    )
    (net (code "85") (name "unconnected-(S3-PadA)") (class "Default")
      (node (ref "S3") (pin "A") (pinfunction "A_A") (pintype "passive"))
    )
    (net (code "86") (name "unconnected-(S4-C-PadK)") (class "Default")
      (node (ref "S4") (pin "K") (pinfunction "C_K") (pintype "passive"))
    )
    (net (code "87") (name "unconnected-(S4-PadA)") (class "Default")
      (node (ref "S4") (pin "A") (pinfunction "A_A") (pintype "passive"))
    )
    (net (code "88") (name "unconnected-(S5-C-PadK)") (class "Default")
      (node (ref "S5") (pin "K") (pinfunction "C_K") (pintype "passive"))
    )
    (net (code "89") (name "unconnected-(S5-PadA)") (class "Default")
      (node (ref "S5") (pin "A") (pinfunction "A_A") (pintype "passive"))
    )
    (net (code "90") (name "unconnected-(S6-S-Pad3)") (class "Default")
      (node (ref "S6") (pin "3") (pinfunction "S_3") (pintype "passive"))
    )
    (net (code "91") (name "unconnected-(S7-C-PadK)") (class "Default")
      (node (ref "S7") (pin "K") (pinfunction "C_K") (pintype "passive"))
    )
    (net (code "92") (name "unconnected-(S7-PadA)") (class "Default")
      (node (ref "S7") (pin "A") (pinfunction "A_A") (pintype "passive"))
    )
    (net (code "93") (name "unconnected-(S8-C-PadK)") (class "Default")
      (node (ref "S8") (pin "K") (pinfunction "C_K") (pintype "passive"))
    )
    (net (code "94") (name "unconnected-(S8-PadA)") (class "Default")
      (node (ref "S8") (pin "A") (pinfunction "A_A") (pintype "passive"))
    )
  )
)
